# cs301_07.net
KiCad netlist of a schematic drawn in Altium Designer
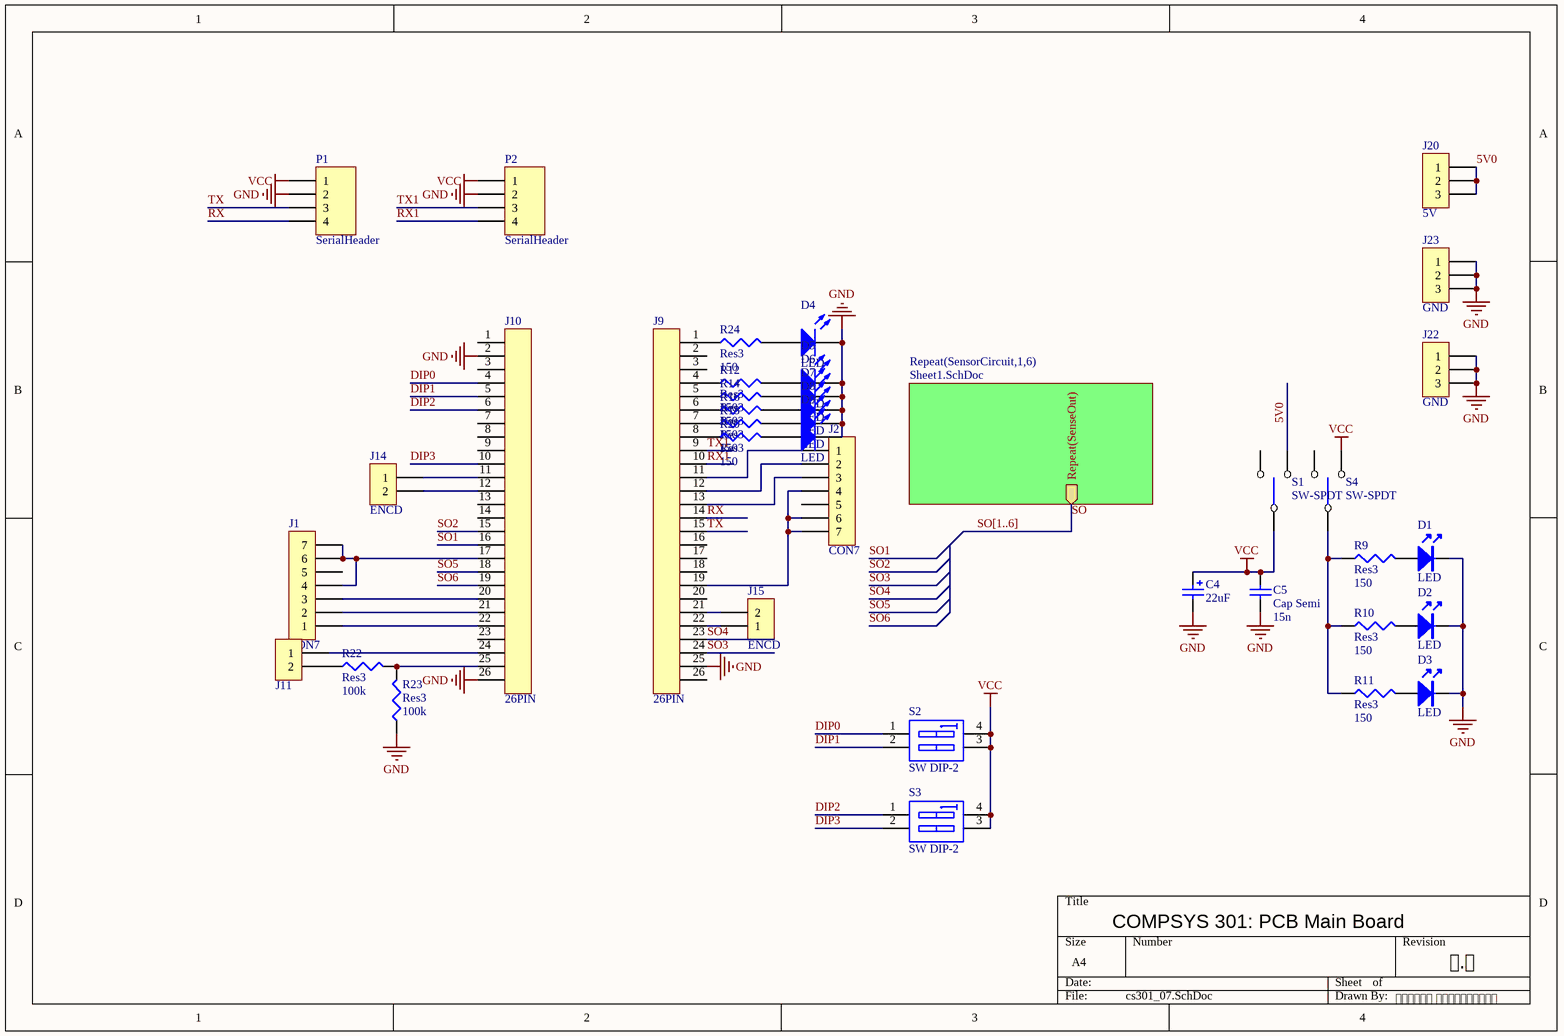
[diagram p0: cs301_07.SchDoc]

(export (version "E")
  (design (tool "Eeschema 10.0.6"))
  (components
    (comp (ref "C4")
      (value "22uF")
      (footprint "ECE-CAPAE6.3X5.4SM")
      (description "Polarized Capacitor (Radial)")
      (libsource (lib "EE209-SMT") (part "CAP 22uF/35V SM"))
    )
    (comp (ref "C5")
      (value "Cap Semi")
      (footprint "1608[0603]")
      (description "Capacitor (Semiconductor SIM Model)")
      (fields (field (name "ALTIUM_VALUE") "15n") (field (name "PUBLISHER") "Altium Limited"))
      (libsource (lib "Miscellaneous Devices") (part "Cap Semi"))
    )
    (comp (ref "D1") (value "LED") (footprint "LED0.1/5MM") (libsource (lib "COMSYS301_2013") (part "LED")))
    (comp (ref "D2") (value "LED") (footprint "LED0.1/5MM") (libsource (lib "COMSYS301_2013") (part "LED")))
    (comp (ref "D3") (value "LED") (footprint "LED0.1/5MM") (libsource (lib "COMSYS301_2013") (part "LED")))
    (comp (ref "D4")
      (value "LED")
      (footprint "ECE-LED2012-0805SM")
      (description "LED GREEN CLEAR 0805 SM")
      (libsource (lib "EceParts") (part "LED"))
    )
    (comp (ref "D5")
      (value "LED")
      (footprint "ECE-LED2012-0805SM")
      (description "LED GREEN CLEAR 0805 SM")
      (libsource (lib "EceParts") (part "LED"))
    )
    (comp (ref "D6")
      (value "LED")
      (footprint "ECE-LED2012-0805SM")
      (description "LED GREEN CLEAR 0805 SM")
      (libsource (lib "EceParts") (part "LED"))
    )
    (comp (ref "D7")
      (value "LED")
      (footprint "ECE-LED2012-0805SM")
      (description "LED GREEN CLEAR 0805 SM")
      (libsource (lib "EceParts") (part "LED"))
    )
    (comp (ref "D8")
      (value "LED")
      (footprint "ECE-LED2012-0805SM")
      (description "LED GREEN CLEAR 0805 SM")
      (libsource (lib "EceParts") (part "LED"))
    )
    (comp (ref "D9")
      (value "LED")
      (footprint "ECE-LED2012-0805SM")
      (description "LED GREEN CLEAR 0805 SM")
      (libsource (lib "EceParts") (part "LED"))
    )
    (comp (ref "J1")
      (value "CON7")
      (footprint "SIP7")
      (description "Connector")
      (libsource (lib "Miscellaneous Devices") (part "CON7"))
    )
    (comp (ref "J2")
      (value "CON7")
      (footprint "SIP7")
      (description "Connector")
      (libsource (lib "") (part "CON7_1"))
    )
    (comp (ref "J9") (value "26PIN") (footprint "SIP26") (libsource (lib "") (part "26PIN_1")))
    (comp (ref "J10")
      (value "26PIN")
      (footprint "SIP26")
      (libsource (lib "Miscellaneous Devices") (part "26PIN"))
    )
    (comp (ref "J11")
      (value "Battery")
      (footprint "sip2")
      (description "Connector")
      (libsource (lib "Miscellaneous Devices") (part "CON2"))
    )
    (comp (ref "J14")
      (value "ENCD")
      (footprint "sip2")
      (description "Connector")
      (libsource (lib "Miscellaneous Devices") (part "CON2"))
    )
    (comp (ref "J15")
      (value "ENCD")
      (footprint "sip2")
      (description "Connector")
      (libsource (lib "") (part "CON2_1"))
    )
    (comp (ref "J20")
      (value "5V")
      (footprint "sip3")
      (description "Connector")
      (libsource (lib "Miscellaneous Devices") (part "CON3"))
    )
    (comp (ref "J22")
      (value "GND")
      (footprint "sip3")
      (description "Connector")
      (libsource (lib "Miscellaneous Devices") (part "CON3"))
    )
    (comp (ref "J23")
      (value "GND")
      (footprint "sip3")
      (description "Connector")
      (libsource (lib "Miscellaneous Devices") (part "CON3"))
    )
    (comp (ref "P1")
      (value "SerialHeader")
      (footprint "HDR1X4")
      (description "Header, 4-Pin")
      (fields (field (name "PUBLISHER") "Altium Limited"))
      (libsource (lib "Miscellaneous Connectors") (part "Header 4"))
    )
    (comp (ref "P2")
      (value "SerialHeader")
      (footprint "HDR1X4")
      (description "Header, 4-Pin")
      (fields (field (name "PUBLISHER") "Altium Limited"))
      (libsource (lib "Miscellaneous Connectors") (part "Header 4"))
    )
    (comp (ref "R9")
      (value "Res3")
      (footprint "J1-0603")
      (description "Resistor")
      (fields (field (name "ALTIUM_VALUE") "150") (field (name "PUBLISHER") "Altium Limited"))
      (libsource (lib "Miscellaneous Devices") (part "Res3"))
    )
    (comp (ref "R10")
      (value "Res3")
      (footprint "J1-0603")
      (description "Resistor")
      (fields (field (name "ALTIUM_VALUE") "150") (field (name "PUBLISHER") "Altium Limited"))
      (libsource (lib "Miscellaneous Devices") (part "Res3"))
    )
    (comp (ref "R11")
      (value "Res3")
      (footprint "J1-0603")
      (description "Resistor")
      (fields (field (name "ALTIUM_VALUE") "150") (field (name "PUBLISHER") "Altium Limited"))
      (libsource (lib "Miscellaneous Devices") (part "Res3"))
    )
    (comp (ref "R12")
      (value "Res3")
      (footprint "J1-0603")
      (description "Resistor")
      (fields (field (name "ALTIUM_VALUE") "150") (field (name "PUBLISHER") "Altium Limited"))
      (libsource (lib "Miscellaneous Devices") (part "Res3"))
    )
    (comp (ref "R14")
      (value "Res3")
      (footprint "J1-0603")
      (description "Resistor")
      (fields (field (name "ALTIUM_VALUE") "150") (field (name "PUBLISHER") "Altium Limited"))
      (libsource (lib "Miscellaneous Devices") (part "Res3"))
    )
    (comp (ref "R16")
      (value "Res3")
      (footprint "J1-0603")
      (description "Resistor")
      (fields (field (name "ALTIUM_VALUE") "150") (field (name "PUBLISHER") "Altium Limited"))
      (libsource (lib "Miscellaneous Devices") (part "Res3"))
    )
    (comp (ref "R18")
      (value "Res3")
      (footprint "J1-0603")
      (description "Resistor")
      (fields (field (name "ALTIUM_VALUE") "150") (field (name "PUBLISHER") "Altium Limited"))
      (libsource (lib "Miscellaneous Devices") (part "Res3"))
    )
    (comp (ref "R20")
      (value "Res3")
      (footprint "J1-0603")
      (description "Resistor")
      (fields (field (name "ALTIUM_VALUE") "150") (field (name "PUBLISHER") "Altium Limited"))
      (libsource (lib "Miscellaneous Devices") (part "Res3"))
    )
    (comp (ref "R22")
      (value "Res3")
      (footprint "J1-0603")
      (description "Resistor")
      (fields (field (name "ALTIUM_VALUE") "100k") (field (name "PUBLISHER") "Altium Limited"))
      (libsource (lib "Miscellaneous Devices") (part "Res3"))
    )
    (comp (ref "R23")
      (value "Res3")
      (footprint "J1-0603")
      (description "Resistor")
      (fields (field (name "ALTIUM_VALUE") "100k") (field (name "PUBLISHER") "Altium Limited"))
      (libsource (lib "Miscellaneous Devices") (part "Res3"))
    )
    (comp (ref "R24")
      (value "Res3")
      (footprint "J1-0603")
      (description "Resistor")
      (fields (field (name "ALTIUM_VALUE") "150") (field (name "PUBLISHER") "Altium Limited"))
      (libsource (lib "Miscellaneous Devices") (part "Res3"))
    )
    (comp (ref "S1")
      (value "SW-SPDT")
      (footprint "SW-SPDT")
      (description "Toggle Switch")
      (libsource (lib "COMSYS301_2013") (part "SW-SPDT"))
    )
    (comp (ref "S2")
      (value "SW DIP-2")
      (footprint "DIP-4")
      (description "DIP Switch, 2 Position, SPST")
      (fields (field (name "PUBLISHER") "Altium Limited"))
      (libsource (lib "Miscellaneous Devices") (part "SW DIP-2"))
    )
    (comp (ref "S3")
      (value "SW DIP-2")
      (footprint "DIP-4")
      (description "DIP Switch, 2 Position, SPST")
      (fields (field (name "PUBLISHER") "Altium Limited"))
      (libsource (lib "Miscellaneous Devices") (part "SW DIP-2"))
    )
    (comp (ref "S4")
      (value "SW-SPDT")
      (footprint "SW-SPDT")
      (description "Toggle Switch")
      (libsource (lib "COMSYS301_2013") (part "SW-SPDT"))
    )
  )
  (nets
    (net (code "1") (name "/5V0") (class "Default")
      (node (ref "J20") (pin "1") (pinfunction "1_1") (pintype "passive"))
      (node (ref "J20") (pin "2") (pinfunction "2_2") (pintype "passive"))
      (node (ref "J20") (pin "3") (pinfunction "3_3") (pintype "passive"))
      (node (ref "S1") (pin "3") (pinfunction "3_3") (pintype "passive"))
    )
    (net (code "2") (name "/DIP0") (class "Default")
      (node (ref "J10") (pin "4") (pinfunction "4_4") (pintype "passive"))
      (node (ref "S2") (pin "1") (pinfunction "A1_1") (pintype "passive"))
    )
    (net (code "3") (name "/DIP1") (class "Default")
      (node (ref "J10") (pin "5") (pinfunction "5_5") (pintype "passive"))
      (node (ref "S2") (pin "2") (pinfunction "A2_2") (pintype "passive"))
    )
    (net (code "4") (name "/DIP2") (class "Default")
      (node (ref "J10") (pin "6") (pinfunction "6_6") (pintype "passive"))
      (node (ref "S3") (pin "1") (pinfunction "A1_1") (pintype "passive"))
    )
    (net (code "5") (name "/DIP3") (class "Default")
      (node (ref "J10") (pin "10") (pinfunction "10_10") (pintype "passive"))
      (node (ref "S3") (pin "2") (pinfunction "A2_2") (pintype "passive"))
    )
    (net (code "6") (name "/RX") (class "Default")
      (node (ref "J9") (pin "14") (pinfunction "14_14") (pintype "passive"))
      (node (ref "P1") (pin "4") (pinfunction "4_4") (pintype "passive"))
    )
    (net (code "7") (name "/RX1") (class "Default")
      (node (ref "J9") (pin "10") (pinfunction "10_10") (pintype "passive"))
      (node (ref "P2") (pin "4") (pinfunction "4_4") (pintype "passive"))
    )
    (net (code "9") (name "/SO1") (class "Default")
      (node (ref "J10") (pin "16") (pinfunction "16_16") (pintype "passive"))
    )
    (net (code "10") (name "/SO2") (class "Default")
      (node (ref "J10") (pin "15") (pinfunction "15_15") (pintype "passive"))
    )
    (net (code "11") (name "/SO3") (class "Default")
      (node (ref "J9") (pin "24") (pinfunction "24_24") (pintype "passive"))
    )
    (net (code "12") (name "/SO4") (class "Default")
      (node (ref "J9") (pin "23") (pinfunction "23_23") (pintype "passive"))
    )
    (net (code "13") (name "/SO5") (class "Default")
      (node (ref "J10") (pin "18") (pinfunction "18_18") (pintype "passive"))
    )
    (net (code "14") (name "/SO6") (class "Default")
      (node (ref "J10") (pin "19") (pinfunction "19_19") (pintype "passive"))
    )
    (net (code "16") (name "/TX") (class "Default")
      (node (ref "J9") (pin "15") (pinfunction "15_15") (pintype "passive"))
      (node (ref "P1") (pin "3") (pinfunction "3_3") (pintype "passive"))
    )
    (net (code "17") (name "/TX1") (class "Default")
      (node (ref "J9") (pin "9") (pinfunction "9_9") (pintype "passive"))
      (node (ref "P2") (pin "3") (pinfunction "3_3") (pintype "passive"))
    )
    (net (code "18") (name "GND") (class "Default")
      (node (ref "C4") (pin "2") (pinfunction "2_2") (pintype "passive"))
      (node (ref "C5") (pin "1") (pinfunction "1_1") (pintype "passive"))
      (node (ref "D1") (pin "K") (pinfunction "2_K") (pintype "passive"))
      (node (ref "D2") (pin "K") (pinfunction "2_K") (pintype "passive"))
      (node (ref "D3") (pin "K") (pinfunction "2_K") (pintype "passive"))
      (node (ref "D4") (pin "2") (pinfunction "K_2") (pintype "passive"))
      (node (ref "D5") (pin "2") (pinfunction "K_2") (pintype "passive"))
      (node (ref "D6") (pin "2") (pinfunction "K_2") (pintype "passive"))
      (node (ref "D7") (pin "2") (pinfunction "K_2") (pintype "passive"))
      (node (ref "D8") (pin "2") (pinfunction "K_2") (pintype "passive"))
      (node (ref "D9") (pin "2") (pinfunction "K_2") (pintype "passive"))
      (node (ref "J10") (pin "2") (pinfunction "2_2") (pintype "passive"))
      (node (ref "J10") (pin "26") (pinfunction "26_26") (pintype "passive"))
      (node (ref "J22") (pin "1") (pinfunction "1_1") (pintype "passive"))
      (node (ref "J22") (pin "2") (pinfunction "2_2") (pintype "passive"))
      (node (ref "J22") (pin "3") (pinfunction "3_3") (pintype "passive"))
      (node (ref "J23") (pin "1") (pinfunction "1_1") (pintype "passive"))
      (node (ref "J23") (pin "2") (pinfunction "2_2") (pintype "passive"))
      (node (ref "J23") (pin "3") (pinfunction "3_3") (pintype "passive"))
      (node (ref "J9") (pin "25") (pinfunction "25_25") (pintype "passive"))
      (node (ref "P1") (pin "2") (pinfunction "2_2") (pintype "passive"))
      (node (ref "P2") (pin "2") (pinfunction "2_2") (pintype "passive"))
      (node (ref "R23") (pin "1") (pinfunction "1_1") (pintype "passive"))
    )
    (net (code "19") (name "Net-(D1-1)") (class "Default")
      (node (ref "D1") (pin "A") (pinfunction "1_A") (pintype "passive"))
      (node (ref "R9") (pin "2") (pinfunction "2_2") (pintype "passive"))
    )
    (net (code "20") (name "Net-(D2-1)") (class "Default")
      (node (ref "D2") (pin "A") (pinfunction "1_A") (pintype "passive"))
      (node (ref "R10") (pin "2") (pinfunction "2_2") (pintype "passive"))
    )
    (net (code "21") (name "Net-(D3-1)") (class "Default")
      (node (ref "D3") (pin "A") (pinfunction "1_A") (pintype "passive"))
      (node (ref "R11") (pin "2") (pinfunction "2_2") (pintype "passive"))
    )
    (net (code "22") (name "Net-(D4-A)") (class "Default")
      (node (ref "D4") (pin "1") (pinfunction "A_1") (pintype "passive"))
      (node (ref "R24") (pin "2") (pinfunction "2_2") (pintype "passive"))
    )
    (net (code "23") (name "Net-(D5-A)") (class "Default")
      (node (ref "D5") (pin "1") (pinfunction "A_1") (pintype "passive"))
      (node (ref "R12") (pin "2") (pinfunction "2_2") (pintype "passive"))
    )
    (net (code "24") (name "Net-(D6-A)") (class "Default")
      (node (ref "D6") (pin "1") (pinfunction "A_1") (pintype "passive"))
      (node (ref "R14") (pin "2") (pinfunction "2_2") (pintype "passive"))
    )
    (net (code "25") (name "Net-(D7-A)") (class "Default")
      (node (ref "D7") (pin "1") (pinfunction "A_1") (pintype "passive"))
      (node (ref "R16") (pin "2") (pinfunction "2_2") (pintype "passive"))
    )
    (net (code "26") (name "Net-(D8-A)") (class "Default")
      (node (ref "D8") (pin "1") (pinfunction "A_1") (pintype "passive"))
      (node (ref "R18") (pin "2") (pinfunction "2_2") (pintype "passive"))
    )
    (net (code "27") (name "Net-(D9-A)") (class "Default")
      (node (ref "D9") (pin "1") (pinfunction "A_1") (pintype "passive"))
      (node (ref "R20") (pin "2") (pinfunction "2_2") (pintype "passive"))
    )
    (net (code "28") (name "Net-(J1-Pad1)") (class "Default")
      (node (ref "J1") (pin "1") (pinfunction "1_1") (pintype "passive"))
      (node (ref "J10") (pin "22") (pinfunction "22_22") (pintype "passive"))
    )
    (net (code "29") (name "Net-(J1-Pad2)") (class "Default")
      (node (ref "J1") (pin "2") (pinfunction "2_2") (pintype "passive"))
      (node (ref "J10") (pin "21") (pinfunction "21_21") (pintype "passive"))
    )
    (net (code "30") (name "Net-(J1-Pad3)") (class "Default")
      (node (ref "J1") (pin "3") (pinfunction "3_3") (pintype "passive"))
      (node (ref "J10") (pin "20") (pinfunction "20_20") (pintype "passive"))
    )
    (net (code "31") (name "Net-(J1-Pad4)") (class "Default")
      (node (ref "J1") (pin "4") (pinfunction "4_4") (pintype "passive"))
      (node (ref "J1") (pin "6") (pinfunction "6_6") (pintype "passive"))
      (node (ref "J1") (pin "7") (pinfunction "7_7") (pintype "passive"))
      (node (ref "J10") (pin "17") (pinfunction "17_17") (pintype "passive"))
    )
    (net (code "32") (name "Net-(J2-Pad1)") (class "Default")
      (node (ref "J2") (pin "1") (pinfunction "1_1") (pintype "passive"))
      (node (ref "J9") (pin "11") (pinfunction "11_11") (pintype "passive"))
    )
    (net (code "33") (name "Net-(J2-Pad2)") (class "Default")
      (node (ref "J2") (pin "2") (pinfunction "2_2") (pintype "passive"))
      (node (ref "J9") (pin "12") (pinfunction "12_12") (pintype "passive"))
    )
    (net (code "34") (name "Net-(J2-Pad3)") (class "Default")
      (node (ref "J2") (pin "3") (pinfunction "3_3") (pintype "passive"))
      (node (ref "J9") (pin "13") (pinfunction "13_13") (pintype "passive"))
    )
    (net (code "35") (name "Net-(J2-Pad4)") (class "Default")
      (node (ref "J2") (pin "4") (pinfunction "4_4") (pintype "passive"))
      (node (ref "J2") (pin "6") (pinfunction "6_6") (pintype "passive"))
      (node (ref "J2") (pin "7") (pinfunction "7_7") (pintype "passive"))
      (node (ref "J9") (pin "19") (pinfunction "19_19") (pintype "passive"))
    )
    (net (code "36") (name "Net-(J9-Pad1)") (class "Default")
      (node (ref "J9") (pin "1") (pinfunction "1_1") (pintype "passive"))
      (node (ref "R24") (pin "1") (pinfunction "1_1") (pintype "passive"))
    )
    (net (code "37") (name "Net-(J9-Pad4)") (class "Default")
      (node (ref "J9") (pin "4") (pinfunction "4_4") (pintype "passive"))
      (node (ref "R12") (pin "1") (pinfunction "1_1") (pintype "passive"))
    )
    (net (code "38") (name "Net-(J9-Pad5)") (class "Default")
      (node (ref "J9") (pin "5") (pinfunction "5_5") (pintype "passive"))
      (node (ref "R14") (pin "1") (pinfunction "1_1") (pintype "passive"))
    )
    (net (code "39") (name "Net-(J9-Pad6)") (class "Default")
      (node (ref "J9") (pin "6") (pinfunction "6_6") (pintype "passive"))
      (node (ref "R16") (pin "1") (pinfunction "1_1") (pintype "passive"))
    )
    (net (code "40") (name "Net-(J9-Pad7)") (class "Default")
      (node (ref "J9") (pin "7") (pinfunction "7_7") (pintype "passive"))
      (node (ref "R18") (pin "1") (pinfunction "1_1") (pintype "passive"))
    )
    (net (code "41") (name "Net-(J9-Pad8)") (class "Default")
      (node (ref "J9") (pin "8") (pinfunction "8_8") (pintype "passive"))
      (node (ref "R20") (pin "1") (pinfunction "1_1") (pintype "passive"))
    )
    (net (code "42") (name "Net-(J10-Pad11)") (class "Default")
      (node (ref "J10") (pin "11") (pinfunction "11_11") (pintype "passive"))
      (node (ref "J14") (pin "1") (pinfunction "1_1") (pintype "passive"))
    )
    (net (code "43") (name "Net-(J10-Pad12)") (class "Default")
      (node (ref "J10") (pin "12") (pinfunction "12_12") (pintype "passive"))
      (node (ref "J14") (pin "2") (pinfunction "2_2") (pintype "passive"))
    )
    (net (code "44") (name "Net-(J10-Pad24)") (class "Default")
      (node (ref "J10") (pin "24") (pinfunction "24_24") (pintype "passive"))
      (node (ref "J11") (pin "1") (pinfunction "1_1") (pintype "passive"))
    )
    (net (code "45") (name "Net-(J10-Pad25)") (class "Default")
      (node (ref "J10") (pin "25") (pinfunction "25_25") (pintype "passive"))
      (node (ref "R22") (pin "2") (pinfunction "2_2") (pintype "passive"))
      (node (ref "R23") (pin "2") (pinfunction "2_2") (pintype "passive"))
    )
    (net (code "46") (name "Net-(J11-Pad2)") (class "Default")
      (node (ref "J11") (pin "2") (pinfunction "2_2") (pintype "passive"))
      (node (ref "R22") (pin "1") (pinfunction "1_1") (pintype "passive"))
    )
    (net (code "47") (name "Net-(J15-Pad1)") (class "Default")
      (node (ref "J15") (pin "1") (pinfunction "1_1") (pintype "passive"))
      (node (ref "J9") (pin "22") (pinfunction "22_22") (pintype "passive"))
    )
    (net (code "48") (name "Net-(J15-Pad2)") (class "Default")
      (node (ref "J15") (pin "2") (pinfunction "2_2") (pintype "passive"))
      (node (ref "J9") (pin "21") (pinfunction "21_21") (pintype "passive"))
    )
    (net (code "49") (name "Net-(R10-Pad1)") (class "Default")
      (node (ref "R10") (pin "1") (pinfunction "1_1") (pintype "passive"))
      (node (ref "R11") (pin "1") (pinfunction "1_1") (pintype "passive"))
      (node (ref "R9") (pin "1") (pinfunction "1_1") (pintype "passive"))
      (node (ref "S4") (pin "2") (pinfunction "2_2") (pintype "passive"))
    )
    (net (code "50") (name "VCC") (class "Default")
      (node (ref "C4") (pin "1") (pinfunction "1_1") (pintype "passive"))
      (node (ref "C5") (pin "2") (pinfunction "2_2") (pintype "passive"))
      (node (ref "P1") (pin "1") (pinfunction "1_1") (pintype "passive"))
      (node (ref "P2") (pin "1") (pinfunction "1_1") (pintype "passive"))
      (node (ref "S1") (pin "2") (pinfunction "2_2") (pintype "passive"))
      (node (ref "S2") (pin "3") (pinfunction "B2_3") (pintype "passive"))
      (node (ref "S2") (pin "4") (pinfunction "B1_4") (pintype "passive"))
      (node (ref "S3") (pin "3") (pinfunction "B2_3") (pintype "passive"))
      (node (ref "S3") (pin "4") (pinfunction "B1_4") (pintype "passive"))
      (node (ref "S4") (pin "3") (pinfunction "3_3") (pintype "passive"))
    )
    (net (code "51") (name "unconnected-(J1-Pad5)") (class "Default")
      (node (ref "J1") (pin "5") (pinfunction "5_5") (pintype "passive"))
    )
    (net (code "52") (name "unconnected-(J2-Pad5)") (class "Default")
      (node (ref "J2") (pin "5") (pinfunction "5_5") (pintype "passive"))
    )
    (net (code "53") (name "unconnected-(J9-Pad2)") (class "Default")
      (node (ref "J9") (pin "2") (pinfunction "2_2") (pintype "passive"))
    )
    (net (code "54") (name "unconnected-(J9-Pad3)") (class "Default")
      (node (ref "J9") (pin "3") (pinfunction "3_3") (pintype "passive"))
    )
    (net (code "55") (name "unconnected-(J9-Pad16)") (class "Default")
      (node (ref "J9") (pin "16") (pinfunction "16_16") (pintype "passive"))
    )
    (net (code "56") (name "unconnected-(J9-Pad17)") (class "Default")
      (node (ref "J9") (pin "17") (pinfunction "17_17") (pintype "passive"))
    )
    (net (code "57") (name "unconnected-(J9-Pad18)") (class "Default")
      (node (ref "J9") (pin "18") (pinfunction "18_18") (pintype "passive"))
    )
    (net (code "58") (name "unconnected-(J9-Pad20)") (class "Default")
      (node (ref "J9") (pin "20") (pinfunction "20_20") (pintype "passive"))
    )
    (net (code "59") (name "unconnected-(J9-Pad26)") (class "Default")
      (node (ref "J9") (pin "26") (pinfunction "26_26") (pintype "passive"))
    )
    (net (code "60") (name "unconnected-(J10-Pad1)") (class "Default")
      (node (ref "J10") (pin "1") (pinfunction "1_1") (pintype "passive"))
    )
    (net (code "61") (name "unconnected-(J10-Pad3)") (class "Default")
      (node (ref "J10") (pin "3") (pinfunction "3_3") (pintype "passive"))
    )
    (net (code "62") (name "unconnected-(J10-Pad7)") (class "Default")
      (node (ref "J10") (pin "7") (pinfunction "7_7") (pintype "passive"))
    )
    (net (code "63") (name "unconnected-(J10-Pad8)") (class "Default")
      (node (ref "J10") (pin "8") (pinfunction "8_8") (pintype "passive"))
    )
    (net (code "64") (name "unconnected-(J10-Pad9)") (class "Default")
      (node (ref "J10") (pin "9") (pinfunction "9_9") (pintype "passive"))
    )
    (net (code "65") (name "unconnected-(J10-Pad13)") (class "Default")
      (node (ref "J10") (pin "13") (pinfunction "13_13") (pintype "passive"))
    )
    (net (code "66") (name "unconnected-(J10-Pad14)") (class "Default")
      (node (ref "J10") (pin "14") (pinfunction "14_14") (pintype "passive"))
    )
    (net (code "67") (name "unconnected-(J10-Pad23)") (class "Default")
      (node (ref "J10") (pin "23") (pinfunction "23_23") (pintype "passive"))
    )
    (net (code "68") (name "unconnected-(S1-Pad1)") (class "Default")
      (node (ref "S1") (pin "1") (pinfunction "1_1") (pintype "passive"))
    )
    (net (code "69") (name "unconnected-(S4-Pad1)") (class "Default")
      (node (ref "S4") (pin "1") (pinfunction "1_1") (pintype "passive"))
    )
  )
)
